# vaja1.net
KiCad netlist of a schematic drawn in Altium Designer
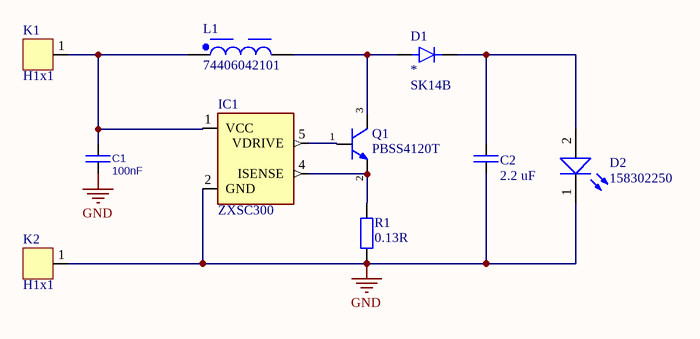
[diagram p0: vaja1.SchDoc]

(export (version "E")
  (design (tool "Eeschema 10.0.6"))
  (components
    (comp (ref "C1")
      (value "100nF")
      (footprint "C0805")
      (description "Capacitor")
      (libsource (lib "University of Ljubljana, Faculty of Electrical Engineering") (part "C"))
    )
    (comp (ref "C2")
      (value "2.2 uF")
      (footprint "C0805(2012)_M")
      (description "Capacitor")
      (fields (field (name "SOURCE") "MISKO.SCHLIB"))
      (libsource (lib "") (part "Symbol_1"))
    )
    (comp (ref "D1")
      (value "SK14B")
      (footprint "DIOM4336X265N")
      (fields (field (name "ALTIUM_VALUE") "*"))
      (libsource (lib "University of Ljubljana, Faculty of Electrical Engineering") (part "SK14B"))
    )
    (comp (ref "D2")
      (value "158302250")
      (footprint "WL-SWTP_3022_L3W2H0.8")
      (description "WL-SWTP SMT White Top view PLCC, size 3022, Daylight, 3.2V, 120°")
      (fields (field (name "MANUFACTURER") "Wurth Elektronik"))
      (libsource (lib "University of Ljubljana, Faculty of Electrical Engineering") (part "158563260A"))
    )
    (comp (ref "IC1")
      (value "ZXSC300")
      (footprint "SOT23-5")
      (description "LED Driver 1 Segment 4000uA Supply Current 5-Pin SOT-23 T/R")
      (fields (field (name "MF") "Diodes Zetex"))
      (libsource (lib "University of Ljubljana, Faculty of Electrical Engineering") (part "ZXSC300"))
    )
    (comp (ref "K1")
      (value "H1x1")
      (footprint "H1x1")
      (description "Header 1x1 (male)")
      (libsource (lib "University of Ljubljana, Faculty of Electrical Engineering") (part "H1x1"))
    )
    (comp (ref "K2")
      (value "H1x1")
      (footprint "H1x1")
      (description "Header 1x1 (male)")
      (libsource (lib "University of Ljubljana, Faculty of Electrical Engineering") (part "H1x1"))
    )
    (comp (ref "L1")
      (value "74406042101")
      (footprint "WE-LQFS_4818")
      (description "WE-LQFS SMT Power Inductor, size 4818, 100µH, 0.42A, 1386mO")
      (fields (field (name "MANUFACTURER") "Wurth Elektronik"))
      (libsource (lib "University of Ljubljana, Faculty of Electrical Engineering") (part "74406043471"))
    )
    (comp (ref "Q1")
      (value "PBSS4120T")
      (footprint "SOT23-3_N")
      (libsource (lib "University of Ljubljana, Faculty of Electrical Engineering") (part "Transistor BJT NPN"))
    )
    (comp (ref "R1")
      (value "0.13R")
      (footprint "R0805(2012)_M")
      (description "R")
      (fields (field (name "SOURCE") "MISKO.SCHLIB"))
      (libsource (lib "University of Ljubljana, Faculty of Electrical Engineering") (part "Symbol"))
    )
  )
  (nets
    (net (code "1") (name "GND") (class "Default")
      (node (ref "C1") (pin "2") (pinfunction "2_2") (pintype "passive"))
      (node (ref "C2") (pin "2") (pinfunction "2_2") (pintype "passive"))
      (node (ref "D2") (pin "1") (pinfunction "K_1") (pintype "passive"))
      (node (ref "IC1") (pin "2") (pinfunction "GND_2") (pintype "power_in"))
      (node (ref "K2") (pin "1") (pinfunction "1_1") (pintype "passive"))
      (node (ref "R1") (pin "2") (pintype "passive"))
    )
    (net (code "2") (name "Net-(D1-K)") (class "Default")
      (node (ref "C2") (pin "1") (pinfunction "1_1") (pintype "passive"))
      (node (ref "D1") (pin "C") (pinfunction "K_C") (pintype "passive"))
      (node (ref "D2") (pin "2") (pinfunction "A_2") (pintype "passive"))
    )
    (net (code "3") (name "Net-(IC1-ISENSE)") (class "Default")
      (node (ref "IC1") (pin "4") (pinfunction "ISENSE_4") (pintype "output"))
      (node (ref "Q1") (pin "2") (pinfunction "E_2") (pintype "passive"))
      (node (ref "R1") (pin "1") (pintype "passive"))
    )
    (net (code "4") (name "Net-(IC1-VCC)") (class "Default")
      (node (ref "C1") (pin "1") (pinfunction "1_1") (pintype "passive"))
      (node (ref "IC1") (pin "1") (pinfunction "VCC_1") (pintype "power_in"))
      (node (ref "K1") (pin "1") (pinfunction "1_1") (pintype "passive"))
      (node (ref "L1") (pin "1") (pinfunction "1_1") (pintype "passive"))
    )
    (net (code "5") (name "Net-(IC1-VDRIVE)") (class "Default")
      (node (ref "IC1") (pin "5") (pinfunction "VDRIVE_5") (pintype "output"))
      (node (ref "Q1") (pin "1") (pinfunction "B_1") (pintype "passive"))
    )
    (net (code "6") (name "Net-(Q1-C)") (class "Default")
      (node (ref "D1") (pin "A") (pinfunction "A_A") (pintype "passive"))
      (node (ref "L1") (pin "2") (pinfunction "2_2") (pintype "passive"))
      (node (ref "Q1") (pin "3") (pinfunction "C_3") (pintype "passive"))
    )
  )
)
